# Current_SENSOR.net
KiCad netlist of a schematic drawn in Altium Designer
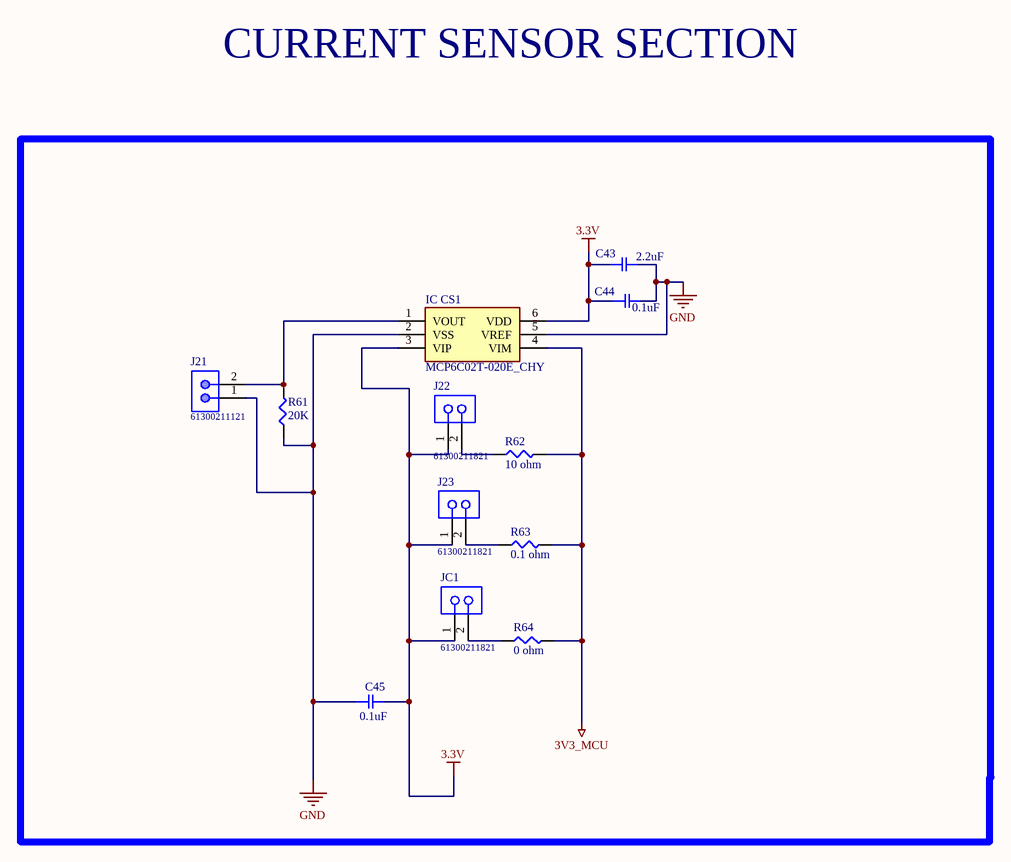
[diagram p0: Current SENSOR.SchDoc]

(export (version "E")
  (design (tool "Eeschema 10.0.6"))
  (components
    (comp (ref "C43")
      (value "2.2uF")
      (footprint "SMD-0805C")
      (description "CAP CER 0.1UF 50V X7R 0805")
      (fields
        (field (name "DIGI-KEY PART NUMBER") "490-11955-1-ND")
        (field (name "PART NUMBER") "GCD21BR71H104KA01L")
      )
      (libsource (lib "capacitor_murata_0805") (part "GCD21BR71H104KA01L"))
    )
    (comp (ref "C44")
      (value "0.1uF")
      (footprint "SMD-0805C")
      (description "CAP CER 0.1UF 50V X7R 0805")
      (fields
        (field (name "DIGI-KEY PART NUMBER") "490-11955-1-ND")
        (field (name "PART NUMBER") "GCD21BR71H104KA01L")
      )
      (libsource (lib "capacitor_murata_0805") (part "GCD21BR71H104KA01L"))
    )
    (comp (ref "C45")
      (value "0.1uF")
      (footprint "SMD-0805C")
      (description "CAP CER 0.1UF 50V X7R 0805")
      (fields
        (field (name "DIGI-KEY PART NUMBER") "490-11955-1-ND")
        (field (name "PART NUMBER") "GCD21BR71H104KA01L")
      )
      (libsource (lib "capacitor_murata_0805") (part "GCD21BR71H104KA01L"))
    )
    (comp (ref "IC CS1")
      (value "MCP6C02T-020E_CHY")
      (footprint "SamacSys:SOT95P280X145-6N")
      (description "Integrated Circuit")
      (fields
        (field (name "MANUFACTURER_PART_NUMBER") "MCP6C02T-020E/CHY")
        (field (name "MOUSER PART NUMBER") "579-MCP6C02T020ECHY")
      )
      (libsource (lib "*") (part "MCP6C02T-020E_CHY"))
    )
    (comp (ref "J21")
      (value "61300211121")
      (footprint "61300211121")
      (description "WR-PHD Pin Header, THT, pitch 2.54mm, Single Row, Vertical, 2pin")
      (fields (field (name "PUBLISHER") "Wurth Elektronik"))
      (libsource (lib "SIL_Connectors WR-PHD_rev19a") (part "61300211121"))
    )
    (comp (ref "J22")
      (value "61300211821")
      (footprint "61300211821")
      (description "WR-PHD Socket Header, THT, pitch 2.54mm, Single Row, Vertical, 2pin")
      (fields (field (name "PUBLISHER") "Wurth Elektronik"))
      (libsource (lib "SIL_Connectors WR-PHD_rev19a") (part "61300211821"))
    )
    (comp (ref "J23")
      (value "61300211821")
      (footprint "61300211821")
      (description "WR-PHD Socket Header, THT, pitch 2.54mm, Single Row, Vertical, 2pin")
      (fields (field (name "PUBLISHER") "Wurth Elektronik"))
      (libsource (lib "SIL_Connectors WR-PHD_rev19a") (part "61300211821"))
    )
    (comp (ref "JC1")
      (value "61300211821")
      (footprint "61300211821")
      (description "WR-PHD Socket Header, THT, pitch 2.54mm, Single Row, Vertical, 2pin")
      (fields (field (name "PUBLISHER") "Wurth Elektronik"))
      (libsource (lib "SIL_Connectors WR-PHD_rev19a") (part "61300211821"))
    )
    (comp (ref "R61")
      (value "20K")
      (footprint "SMD-0805-RES")
      (description "RES SMD 1M OHM 5% 1/2W 0805")
      (fields (field (name "PART NUMBER") "ERJ-P6WJ105V") (field (name "DIGI-KEY PART NUMBER") "P16990CT-ND"))
      (libsource (lib "Panasonic_ERJ_0805") (part "ERJ-P6WJ105V"))
    )
    (comp (ref "R62")
      (value "10 ohm")
      (footprint "SMD-1206-RES")
      (description "RES SMD 0.22 OHM 1% 1/2W 1206")
      (fields (field (name "PART NUMBER") "ERJ-8BQFR22V") (field (name "DIGI-KEY PART NUMBER") "P17624CT-ND"))
      (libsource (lib "Panasonic_ERJ_1206") (part "ERJ-8BQFR22V"))
    )
    (comp (ref "R63")
      (value "0.1 ohm")
      (footprint "SMD-0805-RES")
      (description "RES SMD 0.1 OHM 5% 1/4W 0805")
      (fields (field (name "PART NUMBER") "ERJ-S6SJR10V") (field (name "DIGI-KEY PART NUMBER") "P.1BKCT-ND"))
      (libsource (lib "Panasonic_ERJ_0805") (part "ERJ-S6SJR10V"))
    )
    (comp (ref "R64")
      (value "0 ohm")
      (footprint "SMD-1206-RES")
      (description "RES SMD 0.22 OHM 1% 1/2W 1206")
      (fields (field (name "PART NUMBER") "ERJ-8BQFR22V") (field (name "DIGI-KEY PART NUMBER") "P17624CT-ND"))
      (libsource (lib "Panasonic_ERJ_1206") (part "ERJ-8BQFR22V"))
    )
  )
  (nets
    (net (code "1") (name "3.3V") (class "Default")
      (node (ref "C43") (pin "1") (pinfunction "1_1") (pintype "passive"))
      (node (ref "C44") (pin "1") (pinfunction "1_1") (pintype "passive"))
      (node (ref "C45") (pin "2") (pinfunction "2_2") (pintype "passive"))
      (node (ref "IC CS1") (pin "3") (pinfunction "VIP_3") (pintype "passive"))
      (node (ref "IC CS1") (pin "6") (pinfunction "VDD_6") (pintype "passive"))
      (node (ref "J22") (pin "1") (pinfunction "1_1") (pintype "passive"))
      (node (ref "J23") (pin "1") (pinfunction "1_1") (pintype "passive"))
      (node (ref "JC1") (pin "1") (pinfunction "1_1") (pintype "passive"))
    )
    (net (code "2") (name "3V3_MCU") (class "Default")
      (node (ref "IC CS1") (pin "4") (pinfunction "VIM_4") (pintype "passive"))
      (node (ref "R62") (pin "2") (pinfunction "2_2") (pintype "passive"))
      (node (ref "R63") (pin "2") (pinfunction "2_2") (pintype "passive"))
      (node (ref "R64") (pin "2") (pinfunction "2_2") (pintype "passive"))
    )
    (net (code "3") (name "GND") (class "Default")
      (node (ref "C43") (pin "2") (pinfunction "2_2") (pintype "passive"))
      (node (ref "C44") (pin "2") (pinfunction "2_2") (pintype "passive"))
      (node (ref "C45") (pin "1") (pinfunction "1_1") (pintype "passive"))
      (node (ref "IC CS1") (pin "2") (pinfunction "VSS_2") (pintype "passive"))
      (node (ref "IC CS1") (pin "5") (pinfunction "VREF_5") (pintype "passive"))
      (node (ref "J21") (pin "1") (pinfunction "1_1") (pintype "passive"))
      (node (ref "R61") (pin "1") (pinfunction "1_1") (pintype "passive"))
    )
    (net (code "4") (name "Net-(IC CS1-VOUT)") (class "Default")
      (node (ref "IC CS1") (pin "1") (pinfunction "VOUT_1") (pintype "passive"))
      (node (ref "J21") (pin "2") (pinfunction "2_2") (pintype "passive"))
      (node (ref "R61") (pin "2") (pinfunction "2_2") (pintype "passive"))
    )
    (net (code "5") (name "Net-(J22-Pad2)") (class "Default")
      (node (ref "J22") (pin "2") (pinfunction "2_2") (pintype "passive"))
      (node (ref "R62") (pin "1") (pinfunction "1_1") (pintype "passive"))
    )
    (net (code "6") (name "Net-(J23-Pad2)") (class "Default")
      (node (ref "J23") (pin "2") (pinfunction "2_2") (pintype "passive"))
      (node (ref "R63") (pin "1") (pinfunction "1_1") (pintype "passive"))
    )
    (net (code "7") (name "Net-(JC1-Pad2)") (class "Default")
      (node (ref "JC1") (pin "2") (pinfunction "2_2") (pintype "passive"))
      (node (ref "R64") (pin "1") (pinfunction "1_1") (pintype "passive"))
    )
  )
)
